# attinier85-display-shield-mk-1_0.net
KiCad netlist of a schematic drawn in EAGLE
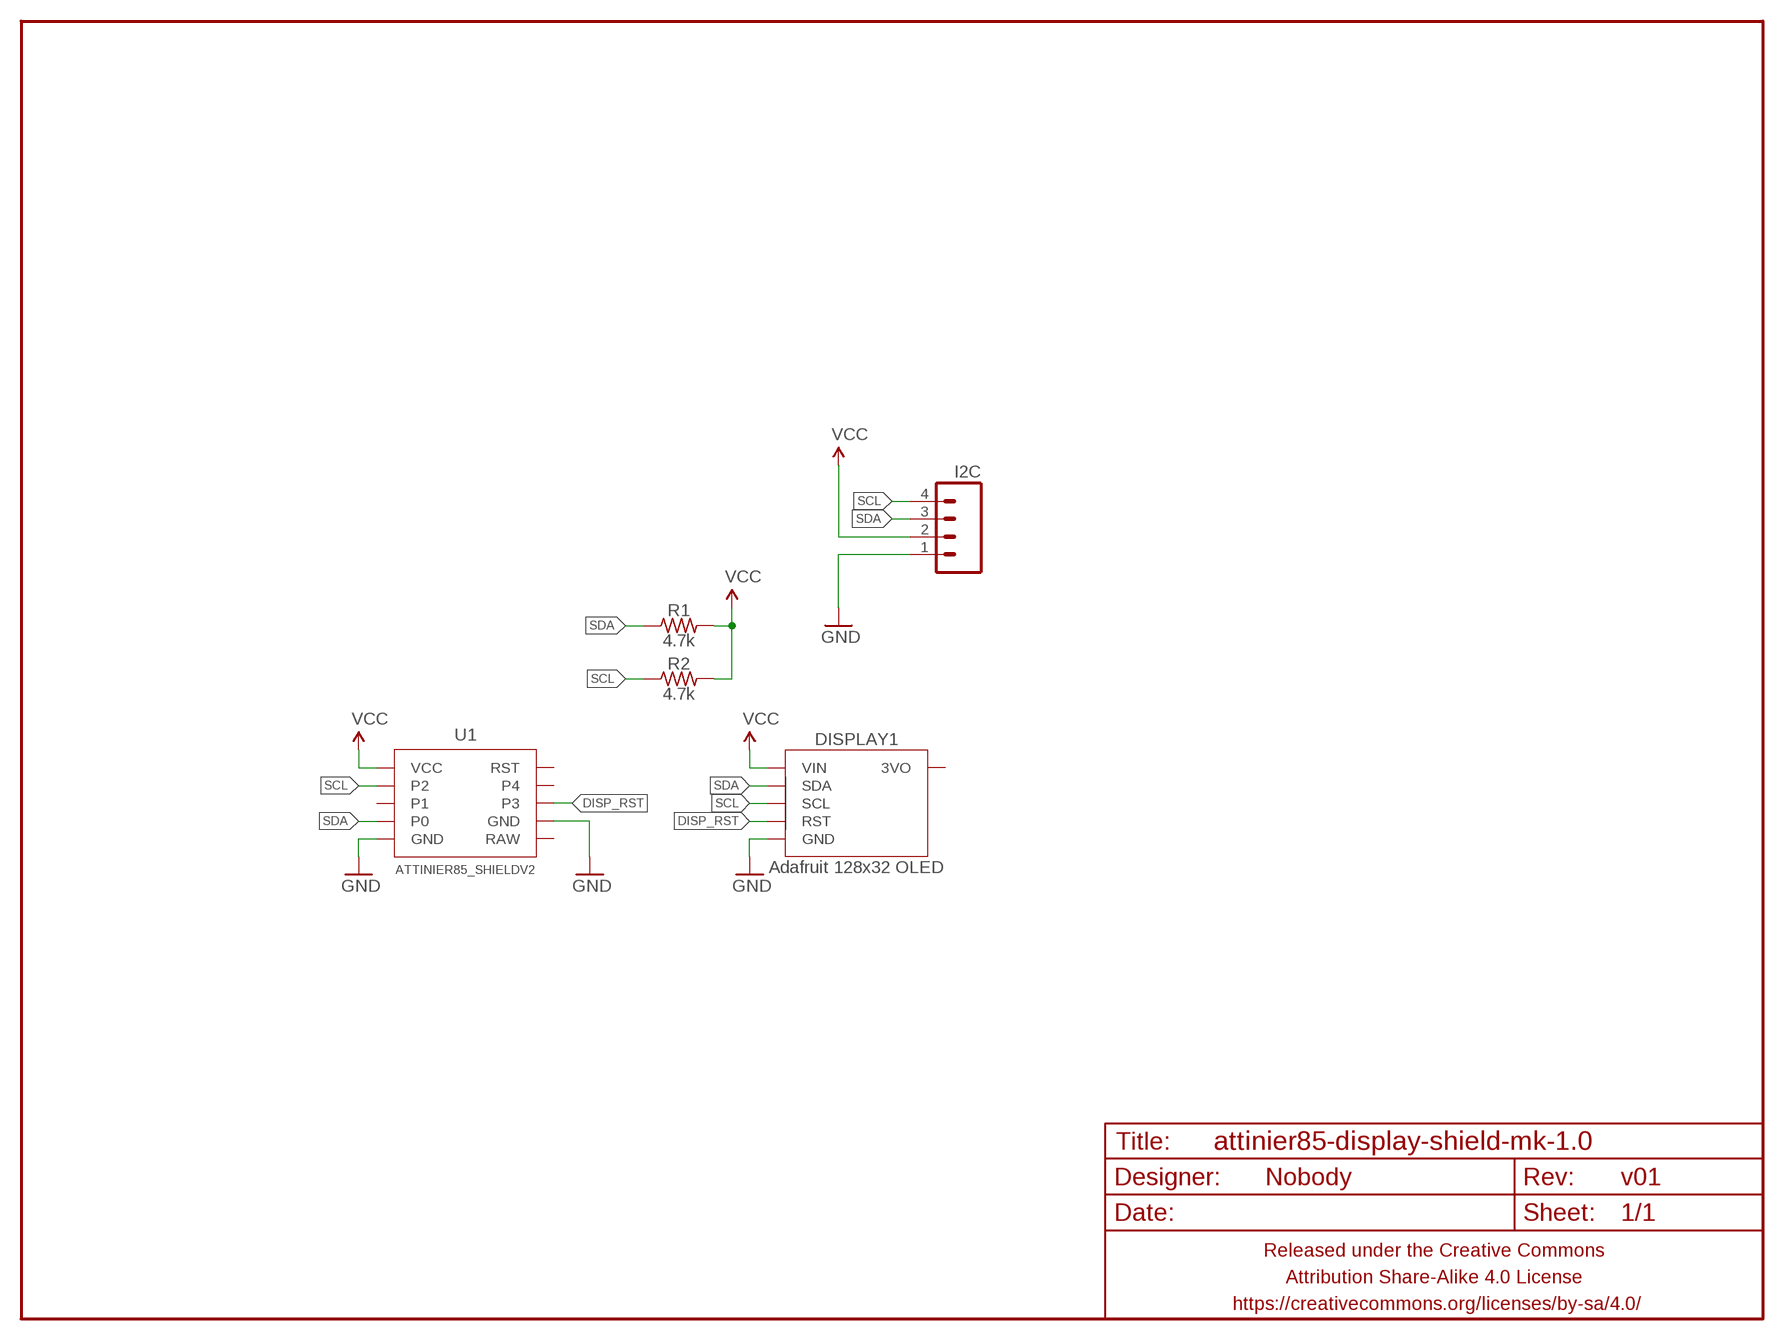
[diagram p0: schematic, sheet 1]

(export (version "E")
  (design (tool "Eeschema 10.0.6"))
  (components
    (comp (ref "DISPLAY1")
      (value "Adafruit 128x32 OLED")
      (footprint "eagle-import:ADAFRUIT_128X32_OLED_I2C_CLOSER_NOHOLES")
      (libsource (lib "eagle-import") (part "ADAFRUIT_128X32_OLED_I2CNOHOLES"))
    )
    (comp (ref "FRAME1")
      (value "FRAME-LETTERNO_PACKAGE")
      (footprint "eagle-import:DUMMY")
      (fields (field (name "DESIGNER") "Nobody"))
      (libsource (lib "eagle-import") (part "FRAME-LETTERNO_PACKAGE"))
    )
    (comp (ref "I2C")
      (value "M04PTH")
      (footprint "eagle-import:1X04-PTH-VERT")
      (libsource (lib "eagle-import") (part "M04PTH"))
    )
    (comp (ref "R1")
      (value "4.7k")
      (footprint "eagle-import:RESISTOR-AXIAL-PTH-7.62MM")
      (libsource (lib "eagle-import") (part "RESISTORPTH-AXIAL-7.62MM"))
    )
    (comp (ref "R2")
      (value "4.7k")
      (footprint "eagle-import:RESISTOR-AXIAL-PTH-7.62MM")
      (libsource (lib "eagle-import") (part "RESISTORPTH-AXIAL-7.62MM"))
    )
    (comp (ref "U1")
      (value "ATTINIER85_SHIELDV2")
      (footprint "eagle-import:ATTINIER85_SHIELD_V2")
      (libsource (lib "eagle-import") (part "ATTINIER85_SHIELDV2"))
    )
  )
  (nets
    (net (code "1") (name "DISP_RST") (class "Default")
      (node (ref "DISPLAY1") (pin "RST") (pinfunction "RST_RST") (pintype "bidirectional"))
      (node (ref "U1") (pin "3") (pinfunction "P3_3") (pintype "bidirectional"))
    )
    (net (code "2") (name "GND") (class "Default")
      (node (ref "DISPLAY1") (pin "GND") (pinfunction "GND_GND") (pintype "bidirectional"))
      (node (ref "I2C") (pin "1") (pinfunction "1_1") (pintype "passive"))
      (node (ref "U1") (pin "GND@1") (pinfunction "GND_GND@1") (pintype "bidirectional"))
      (node (ref "U1") (pin "GND@2") (pinfunction "GND_GND@2") (pintype "bidirectional"))
    )
    (net (code "3") (name "SCL") (class "Default")
      (node (ref "DISPLAY1") (pin "SCL") (pinfunction "SCL_SCL") (pintype "bidirectional"))
      (node (ref "I2C") (pin "4") (pinfunction "4_4") (pintype "passive"))
      (node (ref "R2") (pin "P$1") (pinfunction "1_P$1") (pintype "passive"))
      (node (ref "U1") (pin "2") (pinfunction "P2_2") (pintype "bidirectional"))
    )
    (net (code "4") (name "SDA") (class "Default")
      (node (ref "DISPLAY1") (pin "SDA") (pinfunction "SDA_SDA") (pintype "bidirectional"))
      (node (ref "I2C") (pin "3") (pinfunction "3_3") (pintype "passive"))
      (node (ref "R1") (pin "P$1") (pinfunction "1_P$1") (pintype "passive"))
      (node (ref "U1") (pin "0") (pinfunction "P0_0") (pintype "bidirectional"))
    )
    (net (code "5") (name "VCC") (class "Default")
      (node (ref "DISPLAY1") (pin "VIN") (pinfunction "VIN_VIN") (pintype "bidirectional"))
      (node (ref "I2C") (pin "2") (pinfunction "2_2") (pintype "passive"))
      (node (ref "R1") (pin "P$2") (pinfunction "2_P$2") (pintype "passive"))
      (node (ref "R2") (pin "P$2") (pinfunction "2_P$2") (pintype "passive"))
      (node (ref "U1") (pin "VCC") (pinfunction "VCC_VCC") (pintype "bidirectional"))
    )
    (net (code "6") (name "unconnected-(DISPLAY1-Pad3VO)") (class "Default")
      (node (ref "DISPLAY1") (pin "3VO") (pinfunction "3VO_3VO") (pintype "bidirectional"))
    )
    (net (code "7") (name "unconnected-(U1-P1-Pad1)") (class "Default")
      (node (ref "U1") (pin "1") (pinfunction "P1_1") (pintype "bidirectional"))
    )
    (net (code "8") (name "unconnected-(U1-P4-Pad4)") (class "Default")
      (node (ref "U1") (pin "4") (pinfunction "P4_4") (pintype "bidirectional"))
    )
    (net (code "9") (name "unconnected-(U1-PadRAW)") (class "Default")
      (node (ref "U1") (pin "RAW") (pinfunction "RAW_RAW") (pintype "bidirectional"))
    )
    (net (code "10") (name "unconnected-(U1-PadRST)") (class "Default")
      (node (ref "U1") (pin "RST") (pinfunction "RST_RST") (pintype "bidirectional"))
    )
  )
)
